# DDR3.net
KiCad netlist of a schematic drawn in Altium Designer
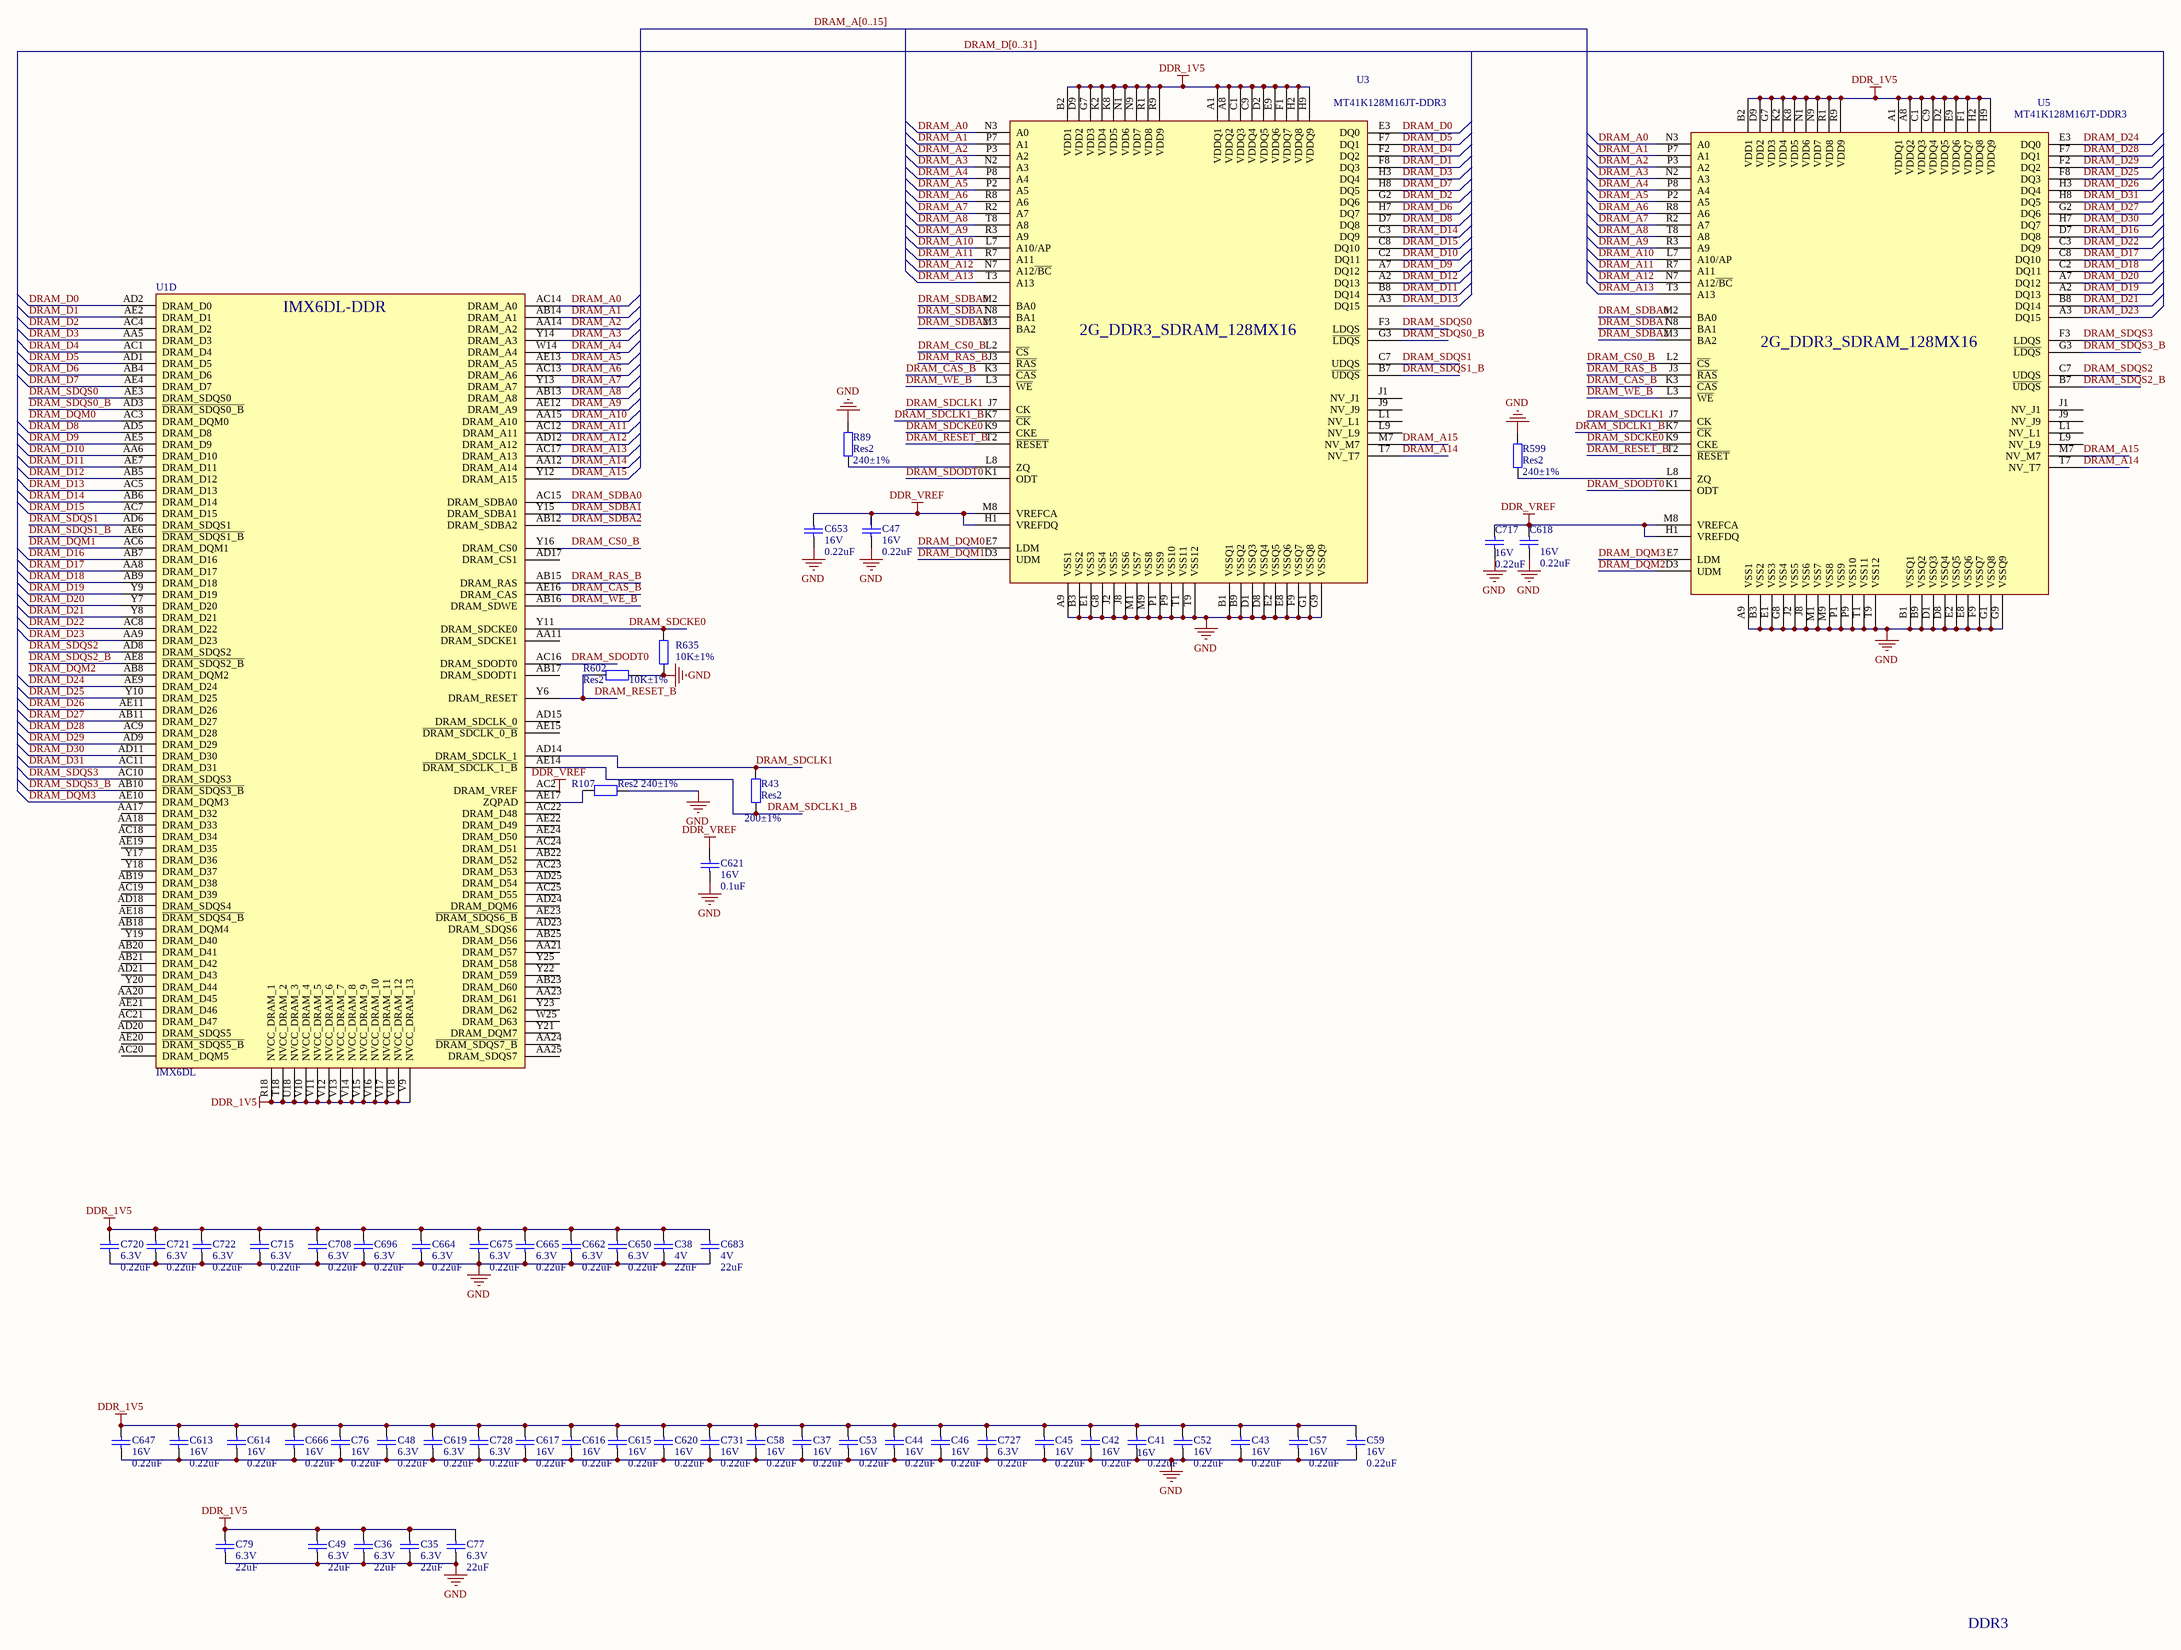
[diagram p0: DDR3.SchDoc]

(export (version "E")
  (design (tool "Eeschema 10.0.6"))
  (components
    (comp (ref "C35")
      (value "6.3V")
      (footprint "0805")
      (description "Capacitor")
      (fields (field (name "ALTIUM_VALUE") "22uF") (field (name "PUBLISHER") "Altium Limited"))
      (libsource (lib "Miscellaneous Devices") (part "Cap"))
    )
    (comp (ref "C36")
      (value "6.3V")
      (footprint "0805")
      (description "Capacitor")
      (fields (field (name "ALTIUM_VALUE") "22uF") (field (name "PUBLISHER") "Altium Limited"))
      (libsource (lib "Miscellaneous Devices") (part "Cap"))
    )
    (comp (ref "C37")
      (value "16V")
      (footprint "0402")
      (description "Capacitor")
      (fields (field (name "ALTIUM_VALUE") "0.22uF") (field (name "PUBLISHER") "Altium Limited"))
      (libsource (lib "Miscellaneous Devices") (part "Cap"))
    )
    (comp (ref "C38")
      (value "4V")
      (footprint "0603")
      (description "Capacitor")
      (fields (field (name "ALTIUM_VALUE") "22uF") (field (name "PUBLISHER") "Altium Limited"))
      (libsource (lib "Miscellaneous Devices") (part "Cap"))
    )
    (comp (ref "C41")
      (value "16V")
      (footprint "0402")
      (description "Capacitor")
      (fields (field (name "ALTIUM_VALUE") "0.22uF") (field (name "PUBLISHER") "Altium Limited"))
      (libsource (lib "Miscellaneous Devices") (part "Cap"))
    )
    (comp (ref "C42")
      (value "16V")
      (footprint "0402")
      (description "Capacitor")
      (fields (field (name "ALTIUM_VALUE") "0.22uF") (field (name "PUBLISHER") "Altium Limited"))
      (libsource (lib "Miscellaneous Devices") (part "Cap"))
    )
    (comp (ref "C43")
      (value "16V")
      (footprint "0402")
      (description "Capacitor")
      (fields (field (name "ALTIUM_VALUE") "0.22uF") (field (name "PUBLISHER") "Altium Limited"))
      (libsource (lib "Miscellaneous Devices") (part "Cap"))
    )
    (comp (ref "C44")
      (value "16V")
      (footprint "0402")
      (description "Capacitor")
      (fields (field (name "ALTIUM_VALUE") "0.22uF") (field (name "PUBLISHER") "Altium Limited"))
      (libsource (lib "Miscellaneous Devices") (part "Cap"))
    )
    (comp (ref "C45")
      (value "16V")
      (footprint "0402")
      (description "Capacitor")
      (fields (field (name "ALTIUM_VALUE") "0.22uF") (field (name "PUBLISHER") "Altium Limited"))
      (libsource (lib "Miscellaneous Devices") (part "Cap"))
    )
    (comp (ref "C46")
      (value "16V")
      (footprint "0402")
      (description "Capacitor")
      (fields (field (name "ALTIUM_VALUE") "0.22uF") (field (name "PUBLISHER") "Altium Limited"))
      (libsource (lib "Miscellaneous Devices") (part "Cap"))
    )
    (comp (ref "C47")
      (value "16V")
      (footprint "0402")
      (description "Capacitor")
      (fields (field (name "ALTIUM_VALUE") "0.22uF") (field (name "PUBLISHER") "Altium Limited"))
      (libsource (lib "Miscellaneous Devices") (part "Cap"))
    )
    (comp (ref "C48")
      (value "6.3V")
      (footprint "0201")
      (description "Capacitor")
      (fields (field (name "ALTIUM_VALUE") "0.22uF") (field (name "PUBLISHER") "Altium Limited"))
      (libsource (lib "Miscellaneous Devices") (part "Cap"))
    )
    (comp (ref "C49")
      (value "6.3V")
      (footprint "0805")
      (description "Capacitor")
      (fields (field (name "ALTIUM_VALUE") "22uF") (field (name "PUBLISHER") "Altium Limited"))
      (libsource (lib "Miscellaneous Devices") (part "Cap"))
    )
    (comp (ref "C52")
      (value "16V")
      (footprint "0402")
      (description "Capacitor")
      (fields (field (name "ALTIUM_VALUE") "0.22uF") (field (name "PUBLISHER") "Altium Limited"))
      (libsource (lib "Miscellaneous Devices") (part "Cap"))
    )
    (comp (ref "C53")
      (value "16V")
      (footprint "0402")
      (description "Capacitor")
      (fields (field (name "ALTIUM_VALUE") "0.22uF") (field (name "PUBLISHER") "Altium Limited"))
      (libsource (lib "Miscellaneous Devices") (part "Cap"))
    )
    (comp (ref "C57")
      (value "16V")
      (footprint "0402")
      (description "Capacitor")
      (fields (field (name "ALTIUM_VALUE") "0.22uF") (field (name "PUBLISHER") "Altium Limited"))
      (libsource (lib "Miscellaneous Devices") (part "Cap"))
    )
    (comp (ref "C58")
      (value "16V")
      (footprint "0402")
      (description "Capacitor")
      (fields (field (name "ALTIUM_VALUE") "0.22uF") (field (name "PUBLISHER") "Altium Limited"))
      (libsource (lib "Miscellaneous Devices") (part "Cap"))
    )
    (comp (ref "C59")
      (value "16V")
      (footprint "0402")
      (description "Capacitor")
      (fields (field (name "ALTIUM_VALUE") "0.22uF") (field (name "PUBLISHER") "Altium Limited"))
      (libsource (lib "Miscellaneous Devices") (part "Cap"))
    )
    (comp (ref "C76")
      (value "16V")
      (footprint "0402")
      (description "Capacitor")
      (fields (field (name "ALTIUM_VALUE") "0.22uF") (field (name "PUBLISHER") "Altium Limited"))
      (libsource (lib "Miscellaneous Devices") (part "Cap"))
    )
    (comp (ref "C77")
      (value "6.3V")
      (footprint "0805")
      (description "Capacitor")
      (fields (field (name "ALTIUM_VALUE") "22uF") (field (name "PUBLISHER") "Altium Limited"))
      (libsource (lib "Miscellaneous Devices") (part "Cap"))
    )
    (comp (ref "C79")
      (value "6.3V")
      (footprint "0805")
      (description "Capacitor")
      (fields (field (name "ALTIUM_VALUE") "22uF") (field (name "PUBLISHER") "Altium Limited"))
      (libsource (lib "Miscellaneous Devices") (part "Cap"))
    )
    (comp (ref "C613")
      (value "16V")
      (footprint "0402")
      (description "Capacitor")
      (fields (field (name "ALTIUM_VALUE") "0.22uF") (field (name "PUBLISHER") "Altium Limited"))
      (libsource (lib "Miscellaneous Devices") (part "Cap"))
    )
    (comp (ref "C614")
      (value "16V")
      (footprint "0402")
      (description "Capacitor")
      (fields (field (name "ALTIUM_VALUE") "0.22uF") (field (name "PUBLISHER") "Altium Limited"))
      (libsource (lib "Miscellaneous Devices") (part "Cap"))
    )
    (comp (ref "C615")
      (value "16V")
      (footprint "0402")
      (description "Capacitor")
      (fields (field (name "ALTIUM_VALUE") "0.22uF") (field (name "PUBLISHER") "Altium Limited"))
      (libsource (lib "Miscellaneous Devices") (part "Cap"))
    )
    (comp (ref "C616")
      (value "16V")
      (footprint "0402")
      (description "Capacitor")
      (fields (field (name "ALTIUM_VALUE") "0.22uF") (field (name "PUBLISHER") "Altium Limited"))
      (libsource (lib "Miscellaneous Devices") (part "Cap"))
    )
    (comp (ref "C617")
      (value "16V")
      (footprint "0402")
      (description "Capacitor")
      (fields (field (name "ALTIUM_VALUE") "0.22uF") (field (name "PUBLISHER") "Altium Limited"))
      (libsource (lib "Miscellaneous Devices") (part "Cap"))
    )
    (comp (ref "C618")
      (value "16V")
      (footprint "0402")
      (description "Capacitor")
      (fields (field (name "ALTIUM_VALUE") "0.22uF") (field (name "PUBLISHER") "Altium Limited"))
      (libsource (lib "Miscellaneous Devices") (part "Cap"))
    )
    (comp (ref "C619")
      (value "6.3V")
      (footprint "0201")
      (description "Capacitor")
      (fields (field (name "ALTIUM_VALUE") "0.22uF") (field (name "PUBLISHER") "Altium Limited"))
      (libsource (lib "Miscellaneous Devices") (part "Cap"))
    )
    (comp (ref "C620")
      (value "16V")
      (footprint "0402")
      (description "Capacitor")
      (fields (field (name "ALTIUM_VALUE") "0.22uF") (field (name "PUBLISHER") "Altium Limited"))
      (libsource (lib "Miscellaneous Devices") (part "Cap"))
    )
    (comp (ref "C621")
      (value "16V")
      (footprint "0402")
      (description "Capacitor")
      (fields (field (name "ALTIUM_VALUE") "0.1uF") (field (name "PUBLISHER") "Altium Limited"))
      (libsource (lib "Miscellaneous Devices") (part "Cap"))
    )
    (comp (ref "C647")
      (value "16V")
      (footprint "0402")
      (description "Capacitor")
      (fields (field (name "ALTIUM_VALUE") "0.22uF") (field (name "PUBLISHER") "Altium Limited"))
      (libsource (lib "Miscellaneous Devices") (part "Cap"))
    )
    (comp (ref "C650")
      (value "6.3V")
      (footprint "0201")
      (description "Capacitor")
      (fields (field (name "ALTIUM_VALUE") "0.22uF") (field (name "PUBLISHER") "Altium Limited"))
      (libsource (lib "Miscellaneous Devices") (part "Cap"))
    )
    (comp (ref "C653")
      (value "16V")
      (footprint "0402")
      (description "Capacitor")
      (fields (field (name "ALTIUM_VALUE") "0.22uF") (field (name "PUBLISHER") "Altium Limited"))
      (libsource (lib "Miscellaneous Devices") (part "Cap"))
    )
    (comp (ref "C662")
      (value "6.3V")
      (footprint "0201")
      (description "Capacitor")
      (fields (field (name "ALTIUM_VALUE") "0.22uF") (field (name "PUBLISHER") "Altium Limited"))
      (libsource (lib "Miscellaneous Devices") (part "Cap"))
    )
    (comp (ref "C664")
      (value "6.3V")
      (footprint "0201")
      (description "Capacitor")
      (fields (field (name "ALTIUM_VALUE") "0.22uF") (field (name "PUBLISHER") "Altium Limited"))
      (libsource (lib "Miscellaneous Devices") (part "Cap"))
    )
    (comp (ref "C665")
      (value "6.3V")
      (footprint "0201")
      (description "Capacitor")
      (fields (field (name "ALTIUM_VALUE") "0.22uF") (field (name "PUBLISHER") "Altium Limited"))
      (libsource (lib "Miscellaneous Devices") (part "Cap"))
    )
    (comp (ref "C666")
      (value "16V")
      (footprint "0402")
      (description "Capacitor")
      (fields (field (name "ALTIUM_VALUE") "0.22uF") (field (name "PUBLISHER") "Altium Limited"))
      (libsource (lib "Miscellaneous Devices") (part "Cap"))
    )
    (comp (ref "C675")
      (value "6.3V")
      (footprint "0201")
      (description "Capacitor")
      (fields (field (name "ALTIUM_VALUE") "0.22uF") (field (name "PUBLISHER") "Altium Limited"))
      (libsource (lib "Miscellaneous Devices") (part "Cap"))
    )
    (comp (ref "C683")
      (value "4V")
      (footprint "0603")
      (description "Capacitor")
      (fields (field (name "ALTIUM_VALUE") "22uF") (field (name "PUBLISHER") "Altium Limited"))
      (libsource (lib "Miscellaneous Devices") (part "Cap"))
    )
    (comp (ref "C696")
      (value "6.3V")
      (footprint "0201")
      (description "Capacitor")
      (fields (field (name "ALTIUM_VALUE") "0.22uF") (field (name "PUBLISHER") "Altium Limited"))
      (libsource (lib "Miscellaneous Devices") (part "Cap"))
    )
    (comp (ref "C708")
      (value "6.3V")
      (footprint "0201")
      (description "Capacitor")
      (fields (field (name "ALTIUM_VALUE") "0.22uF") (field (name "PUBLISHER") "Altium Limited"))
      (libsource (lib "Miscellaneous Devices") (part "Cap"))
    )
    (comp (ref "C715")
      (value "6.3V")
      (footprint "0201")
      (description "Capacitor")
      (fields (field (name "ALTIUM_VALUE") "0.22uF") (field (name "PUBLISHER") "Altium Limited"))
      (libsource (lib "Miscellaneous Devices") (part "Cap"))
    )
    (comp (ref "C717")
      (value "16V")
      (footprint "0402")
      (description "Capacitor")
      (fields (field (name "ALTIUM_VALUE") "0.22uF") (field (name "PUBLISHER") "Altium Limited"))
      (libsource (lib "Miscellaneous Devices") (part "Cap"))
    )
    (comp (ref "C720")
      (value "6.3V")
      (footprint "0201")
      (description "Capacitor")
      (fields (field (name "ALTIUM_VALUE") "0.22uF") (field (name "PUBLISHER") "Altium Limited"))
      (libsource (lib "Miscellaneous Devices") (part "Cap"))
    )
    (comp (ref "C721")
      (value "6.3V")
      (footprint "0201")
      (description "Capacitor")
      (fields (field (name "ALTIUM_VALUE") "0.22uF") (field (name "PUBLISHER") "Altium Limited"))
      (libsource (lib "Miscellaneous Devices") (part "Cap"))
    )
    (comp (ref "C722")
      (value "6.3V")
      (footprint "0201")
      (description "Capacitor")
      (fields (field (name "ALTIUM_VALUE") "0.22uF") (field (name "PUBLISHER") "Altium Limited"))
      (libsource (lib "Miscellaneous Devices") (part "Cap"))
    )
    (comp (ref "C727")
      (value "6.3V")
      (footprint "0201")
      (description "Capacitor")
      (fields (field (name "ALTIUM_VALUE") "0.22uF") (field (name "PUBLISHER") "Altium Limited"))
      (libsource (lib "Miscellaneous Devices") (part "Cap"))
    )
    (comp (ref "C728")
      (value "6.3V")
      (footprint "0201")
      (description "Capacitor")
      (fields (field (name "ALTIUM_VALUE") "0.22uF") (field (name "PUBLISHER") "Altium Limited"))
      (libsource (lib "Miscellaneous Devices") (part "Cap"))
    )
    (comp (ref "C731")
      (value "16V")
      (footprint "0402")
      (description "Capacitor")
      (fields (field (name "ALTIUM_VALUE") "0.22uF") (field (name "PUBLISHER") "Altium Limited"))
      (libsource (lib "Miscellaneous Devices") (part "Cap"))
    )
    (comp (ref "R43")
      (value "Res2")
      (footprint "0402")
      (description "Resistor")
      (fields (field (name "ALTIUM_VALUE") "200±1%") (field (name "PUBLISHER") "Altium Limited"))
      (libsource (lib "") (part "Res2_1"))
    )
    (comp (ref "R89")
      (value "Res2")
      (footprint "0402")
      (description "Resistor")
      (fields (field (name "ALTIUM_VALUE") "240±1%") (field (name "PUBLISHER") "Altium Limited"))
      (libsource (lib "Miscellaneous Devices") (part "Res2"))
    )
    (comp (ref "R107")
      (value "Res2")
      (footprint "0402")
      (description "Resistor")
      (fields (field (name "ALTIUM_VALUE") "240±1%") (field (name "PUBLISHER") "Altium Limited"))
      (libsource (lib "") (part "Res2_2"))
    )
    (comp (ref "R599")
      (value "Res2")
      (footprint "0402")
      (description "Resistor")
      (fields (field (name "ALTIUM_VALUE") "240±1%") (field (name "PUBLISHER") "Altium Limited"))
      (libsource (lib "Miscellaneous Devices") (part "Res2"))
    )
    (comp (ref "R602")
      (value "Res2")
      (footprint "0402")
      (description "Resistor")
      (fields (field (name "ALTIUM_VALUE") "10K±1%") (field (name "PUBLISHER") "Altium Limited"))
      (libsource (lib "") (part "Res2_2"))
    )
    (comp (ref "R635")
      (value "10K±1%")
      (footprint "0402")
      (description "Resistor")
      (fields (field (name "Comment") "Res2") (field (name "PUBLISHER") "Altium Limited"))
      (libsource (lib "") (part "Res2_1"))
    )
    (comp (ref "U1")
      (value "IMX6DL")
      (footprint "IMX6DL-BGA624x25")
      (libsource (lib "IMX6DL") (part "IMX6DL"))
    )
    (comp (ref "U3")
      (value "MT41K128M16JT-DDR3")
      (footprint "MT41K128M16JT-BGA96")
      (libsource (lib "IMX6DL") (part "MT41K128M16JT-DDR3"))
    )
    (comp (ref "U5")
      (value "MT41K128M16JT-DDR3")
      (footprint "MT41K128M16JT-BGA96")
      (libsource (lib "IMX6DL") (part "MT41K128M16JT-DDR3"))
    )
  )
  (nets
    (net (code "1") (name "/DRAM_A0") (class "Default")
      (node (ref "U1") (pin "AC14") (pinfunction "DRAM_A0_AC14") (pintype "passive"))
      (node (ref "U3") (pin "N3") (pinfunction "A0_N3") (pintype "passive"))
      (node (ref "U5") (pin "N3") (pinfunction "A0_N3") (pintype "passive"))
    )
    (net (code "2") (name "/DRAM_A1") (class "Default")
      (node (ref "U1") (pin "AB14") (pinfunction "DRAM_A1_AB14") (pintype "passive"))
      (node (ref "U3") (pin "P7") (pinfunction "A1_P7") (pintype "passive"))
      (node (ref "U5") (pin "P7") (pinfunction "A1_P7") (pintype "passive"))
    )
    (net (code "3") (name "/DRAM_A2") (class "Default")
      (node (ref "U1") (pin "AA14") (pinfunction "DRAM_A2_AA14") (pintype "passive"))
      (node (ref "U3") (pin "P3") (pinfunction "A2_P3") (pintype "passive"))
      (node (ref "U5") (pin "P3") (pinfunction "A2_P3") (pintype "passive"))
    )
    (net (code "4") (name "/DRAM_A3") (class "Default")
      (node (ref "U1") (pin "Y14") (pinfunction "DRAM_A3_Y14") (pintype "passive"))
      (node (ref "U3") (pin "N2") (pinfunction "A3_N2") (pintype "passive"))
      (node (ref "U5") (pin "N2") (pinfunction "A3_N2") (pintype "passive"))
    )
    (net (code "5") (name "/DRAM_A4") (class "Default")
      (node (ref "U1") (pin "W14") (pinfunction "DRAM_A4_W14") (pintype "passive"))
      (node (ref "U3") (pin "P8") (pinfunction "A4_P8") (pintype "passive"))
      (node (ref "U5") (pin "P8") (pinfunction "A4_P8") (pintype "passive"))
    )
    (net (code "6") (name "/DRAM_A5") (class "Default")
      (node (ref "U1") (pin "AE13") (pinfunction "DRAM_A5_AE13") (pintype "passive"))
      (node (ref "U3") (pin "P2") (pinfunction "A5_P2") (pintype "passive"))
      (node (ref "U5") (pin "P2") (pinfunction "A5_P2") (pintype "passive"))
    )
    (net (code "7") (name "/DRAM_A6") (class "Default")
      (node (ref "U1") (pin "AC13") (pinfunction "DRAM_A6_AC13") (pintype "passive"))
      (node (ref "U3") (pin "R8") (pinfunction "A6_R8") (pintype "passive"))
      (node (ref "U5") (pin "R8") (pinfunction "A6_R8") (pintype "passive"))
    )
    (net (code "8") (name "/DRAM_A7") (class "Default")
      (node (ref "U1") (pin "Y13") (pinfunction "DRAM_A7_Y13") (pintype "passive"))
      (node (ref "U3") (pin "R2") (pinfunction "A7_R2") (pintype "passive"))
      (node (ref "U5") (pin "R2") (pinfunction "A7_R2") (pintype "passive"))
    )
    (net (code "9") (name "/DRAM_A8") (class "Default")
      (node (ref "U1") (pin "AB13") (pinfunction "DRAM_A8_AB13") (pintype "passive"))
      (node (ref "U3") (pin "T8") (pinfunction "A8_T8") (pintype "passive"))
      (node (ref "U5") (pin "T8") (pinfunction "A8_T8") (pintype "passive"))
    )
    (net (code "10") (name "/DRAM_A9") (class "Default")
      (node (ref "U1") (pin "AE12") (pinfunction "DRAM_A9_AE12") (pintype "passive"))
      (node (ref "U3") (pin "R3") (pinfunction "A9_R3") (pintype "passive"))
      (node (ref "U5") (pin "R3") (pinfunction "A9_R3") (pintype "passive"))
    )
    (net (code "11") (name "/DRAM_A10") (class "Default")
      (node (ref "U1") (pin "AA15") (pinfunction "DRAM_A10_AA15") (pintype "passive"))
      (node (ref "U3") (pin "L7") (pinfunction "A10/AP_L7") (pintype "passive"))
      (node (ref "U5") (pin "L7") (pinfunction "A10/AP_L7") (pintype "passive"))
    )
    (net (code "12") (name "/DRAM_A11") (class "Default")
      (node (ref "U1") (pin "AC12") (pinfunction "DRAM_A11_AC12") (pintype "passive"))
      (node (ref "U3") (pin "R7") (pinfunction "A11_R7") (pintype "passive"))
      (node (ref "U5") (pin "R7") (pinfunction "A11_R7") (pintype "passive"))
    )
    (net (code "13") (name "/DRAM_A12") (class "Default")
      (node (ref "U1") (pin "AD12") (pinfunction "DRAM_A12_AD12") (pintype "passive"))
      (node (ref "U3") (pin "N7") (pinfunction "A12~{/BC}_N7") (pintype "passive"))
      (node (ref "U5") (pin "N7") (pinfunction "A12~{/BC}_N7") (pintype "passive"))
    )
    (net (code "14") (name "/DRAM_A13") (class "Default")
      (node (ref "U1") (pin "AC17") (pinfunction "DRAM_A13_AC17") (pintype "passive"))
      (node (ref "U3") (pin "T3") (pinfunction "A13_T3") (pintype "passive"))
      (node (ref "U5") (pin "T3") (pinfunction "A13_T3") (pintype "passive"))
    )
    (net (code "15") (name "/DRAM_A14") (class "Default")
      (node (ref "U1") (pin "AA12") (pinfunction "DRAM_A14_AA12") (pintype "passive"))
      (node (ref "U3") (pin "T7") (pinfunction "NV_T7_T7") (pintype "passive"))
      (node (ref "U5") (pin "T7") (pinfunction "NV_T7_T7") (pintype "passive"))
    )
    (net (code "16") (name "/DRAM_A15") (class "Default")
      (node (ref "U1") (pin "Y12") (pinfunction "DRAM_A15_Y12") (pintype "passive"))
      (node (ref "U3") (pin "M7") (pinfunction "NV_M7_M7") (pintype "passive"))
      (node (ref "U5") (pin "M7") (pinfunction "NV_M7_M7") (pintype "passive"))
    )
    (net (code "18") (name "/DRAM_CAS_B") (class "Default")
      (node (ref "U1") (pin "AE16") (pinfunction "DRAM_CAS_AE16") (pintype "passive"))
      (node (ref "U3") (pin "K3") (pinfunction "~{CAS}_K3") (pintype "passive"))
      (node (ref "U5") (pin "K3") (pinfunction "~{CAS}_K3") (pintype "passive"))
    )
    (net (code "19") (name "/DRAM_CS0_B") (class "Default")
      (node (ref "U1") (pin "Y16") (pinfunction "DRAM_CS0_Y16") (pintype "passive"))
      (node (ref "U3") (pin "L2") (pinfunction "~{CS}_L2") (pintype "passive"))
      (node (ref "U5") (pin "L2") (pinfunction "~{CS}_L2") (pintype "passive"))
    )
    (net (code "20") (name "/DRAM_D0") (class "Default")
      (node (ref "U1") (pin "AD2") (pinfunction "DRAM_D0_AD2") (pintype "passive"))
      (node (ref "U3") (pin "E3") (pinfunction "DQ0_E3") (pintype "passive"))
    )
    (net (code "21") (name "/DRAM_D1") (class "Default")
      (node (ref "U1") (pin "AE2") (pinfunction "DRAM_D1_AE2") (pintype "passive"))
      (node (ref "U3") (pin "F8") (pinfunction "DQ3_F8") (pintype "passive"))
    )
    (net (code "22") (name "/DRAM_D2") (class "Default")
      (node (ref "U1") (pin "AC4") (pinfunction "DRAM_D2_AC4") (pintype "passive"))
      (node (ref "U3") (pin "G2") (pinfunction "DQ6_G2") (pintype "passive"))
    )
    (net (code "23") (name "/DRAM_D3") (class "Default")
      (node (ref "U1") (pin "AA5") (pinfunction "DRAM_D3_AA5") (pintype "passive"))
      (node (ref "U3") (pin "H3") (pinfunction "DQ4_H3") (pintype "passive"))
    )
    (net (code "24") (name "/DRAM_D4") (class "Default")
      (node (ref "U1") (pin "AC1") (pinfunction "DRAM_D4_AC1") (pintype "passive"))
      (node (ref "U3") (pin "F2") (pinfunction "DQ2_F2") (pintype "passive"))
    )
    (net (code "25") (name "/DRAM_D5") (class "Default")
      (node (ref "U1") (pin "AD1") (pinfunction "DRAM_D5_AD1") (pintype "passive"))
      (node (ref "U3") (pin "F7") (pinfunction "DQ1_F7") (pintype "passive"))
    )
    (net (code "26") (name "/DRAM_D6") (class "Default")
      (node (ref "U1") (pin "AB4") (pinfunction "DRAM_D6_AB4") (pintype "passive"))
      (node (ref "U3") (pin "H7") (pinfunction "DQ7_H7") (pintype "passive"))
    )
    (net (code "27") (name "/DRAM_D7") (class "Default")
      (node (ref "U1") (pin "AE4") (pinfunction "DRAM_D7_AE4") (pintype "passive"))
      (node (ref "U3") (pin "H8") (pinfunction "DQ5_H8") (pintype "passive"))
    )
    (net (code "28") (name "/DRAM_D8") (class "Default")
      (node (ref "U1") (pin "AD5") (pinfunction "DRAM_D8_AD5") (pintype "passive"))
      (node (ref "U3") (pin "D7") (pinfunction "DQ8_D7") (pintype "passive"))
    )
    (net (code "29") (name "/DRAM_D9") (class "Default")
      (node (ref "U1") (pin "AE5") (pinfunction "DRAM_D9_AE5") (pintype "passive"))
      (node (ref "U3") (pin "A7") (pinfunction "DQ12_A7") (pintype "passive"))
    )
    (net (code "30") (name "/DRAM_D10") (class "Default")
      (node (ref "U1") (pin "AA6") (pinfunction "DRAM_D10_AA6") (pintype "passive"))
      (node (ref "U3") (pin "C2") (pinfunction "DQ11_C2") (pintype "passive"))
    )
    (net (code "31") (name "/DRAM_D11") (class "Default")
      (node (ref "U1") (pin "AE7") (pinfunction "DRAM_D11_AE7") (pintype "passive"))
      (node (ref "U3") (pin "B8") (pinfunction "DQ14_B8") (pintype "passive"))
    )
    (net (code "32") (name "/DRAM_D12") (class "Default")
      (node (ref "U1") (pin "AB5") (pinfunction "DRAM_D12_AB5") (pintype "passive"))
      (node (ref "U3") (pin "A2") (pinfunction "DQ13_A2") (pintype "passive"))
    )
    (net (code "33") (name "/DRAM_D13") (class "Default")
      (node (ref "U1") (pin "AC5") (pinfunction "DRAM_D13_AC5") (pintype "passive"))
      (node (ref "U3") (pin "A3") (pinfunction "DQ15_A3") (pintype "passive"))
    )
    (net (code "34") (name "/DRAM_D14") (class "Default")
      (node (ref "U1") (pin "AB6") (pinfunction "DRAM_D14_AB6") (pintype "passive"))
      (node (ref "U3") (pin "C3") (pinfunction "DQ9_C3") (pintype "passive"))
    )
    (net (code "35") (name "/DRAM_D15") (class "Default")
      (node (ref "U1") (pin "AC7") (pinfunction "DRAM_D15_AC7") (pintype "passive"))
      (node (ref "U3") (pin "C8") (pinfunction "DQ10_C8") (pintype "passive"))
    )
    (net (code "36") (name "/DRAM_D16") (class "Default")
      (node (ref "U1") (pin "AB7") (pinfunction "DRAM_D16_AB7") (pintype "passive"))
      (node (ref "U5") (pin "D7") (pinfunction "DQ8_D7") (pintype "passive"))
    )
    (net (code "37") (name "/DRAM_D17") (class "Default")
      (node (ref "U1") (pin "AA8") (pinfunction "DRAM_D17_AA8") (pintype "passive"))
      (node (ref "U5") (pin "C8") (pinfunction "DQ10_C8") (pintype "passive"))
    )
    (net (code "38") (name "/DRAM_D18") (class "Default")
      (node (ref "U1") (pin "AB9") (pinfunction "DRAM_D18_AB9") (pintype "passive"))
      (node (ref "U5") (pin "C2") (pinfunction "DQ11_C2") (pintype "passive"))
    )
    (net (code "39") (name "/DRAM_D19") (class "Default")
      (node (ref "U1") (pin "Y9") (pinfunction "DRAM_D19_Y9") (pintype "passive"))
      (node (ref "U5") (pin "A2") (pinfunction "DQ13_A2") (pintype "passive"))
    )
    (net (code "40") (name "/DRAM_D20") (class "Default")
      (node (ref "U1") (pin "Y7") (pinfunction "DRAM_D20_Y7") (pintype "passive"))
      (node (ref "U5") (pin "A7") (pinfunction "DQ12_A7") (pintype "passive"))
    )
    (net (code "41") (name "/DRAM_D21") (class "Default")
      (node (ref "U1") (pin "Y8") (pinfunction "DRAM_D21_Y8") (pintype "passive"))
      (node (ref "U5") (pin "B8") (pinfunction "DQ14_B8") (pintype "passive"))
    )
    (net (code "42") (name "/DRAM_D22") (class "Default")
      (node (ref "U1") (pin "AC8") (pinfunction "DRAM_D22_AC8") (pintype "passive"))
      (node (ref "U5") (pin "C3") (pinfunction "DQ9_C3") (pintype "passive"))
    )
    (net (code "43") (name "/DRAM_D23") (class "Default")
      (node (ref "U1") (pin "AA9") (pinfunction "DRAM_D23_AA9") (pintype "passive"))
      (node (ref "U5") (pin "A3") (pinfunction "DQ15_A3") (pintype "passive"))
    )
    (net (code "44") (name "/DRAM_D24") (class "Default")
      (node (ref "U1") (pin "AE9") (pinfunction "DRAM_D24_AE9") (pintype "passive"))
      (node (ref "U5") (pin "E3") (pinfunction "DQ0_E3") (pintype "passive"))
    )
    (net (code "45") (name "/DRAM_D25") (class "Default")
      (node (ref "U1") (pin "Y10") (pinfunction "DRAM_D25_Y10") (pintype "passive"))
      (node (ref "U5") (pin "F8") (pinfunction "DQ3_F8") (pintype "passive"))
    )
    (net (code "46") (name "/DRAM_D26") (class "Default")
      (node (ref "U1") (pin "AE11") (pinfunction "DRAM_D26_AE11") (pintype "passive"))
      (node (ref "U5") (pin "H3") (pinfunction "DQ4_H3") (pintype "passive"))
    )
    (net (code "47") (name "/DRAM_D27") (class "Default")
      (node (ref "U1") (pin "AB11") (pinfunction "DRAM_D27_AB11") (pintype "passive"))
      (node (ref "U5") (pin "G2") (pinfunction "DQ6_G2") (pintype "passive"))
    )
    (net (code "48") (name "/DRAM_D28") (class "Default")
      (node (ref "U1") (pin "AC9") (pinfunction "DRAM_D28_AC9") (pintype "passive"))
      (node (ref "U5") (pin "F7") (pinfunction "DQ1_F7") (pintype "passive"))
    )
    (net (code "49") (name "/DRAM_D29") (class "Default")
      (node (ref "U1") (pin "AD9") (pinfunction "DRAM_D29_AD9") (pintype "passive"))
      (node (ref "U5") (pin "F2") (pinfunction "DQ2_F2") (pintype "passive"))
    )
    (net (code "50") (name "/DRAM_D30") (class "Default")
      (node (ref "U1") (pin "AD11") (pinfunction "DRAM_D30_AD11") (pintype "passive"))
      (node (ref "U5") (pin "H7") (pinfunction "DQ7_H7") (pintype "passive"))
    )
    (net (code "51") (name "/DRAM_D31") (class "Default")
      (node (ref "U1") (pin "AC11") (pinfunction "DRAM_D31_AC11") (pintype "passive"))
      (node (ref "U5") (pin "H8") (pinfunction "DQ5_H8") (pintype "passive"))
    )
    (net (code "52") (name "/DRAM_DQM0") (class "Default")
      (node (ref "U1") (pin "AC3") (pinfunction "DRAM_DQM0_AC3") (pintype "passive"))
      (node (ref "U3") (pin "E7") (pinfunction "LDM_E7") (pintype "passive"))
    )
    (net (code "53") (name "/DRAM_DQM1") (class "Default")
      (node (ref "U1") (pin "AC6") (pinfunction "DRAM_DQM1_AC6") (pintype "passive"))
      (node (ref "U3") (pin "D3") (pinfunction "UDM_D3") (pintype "passive"))
    )
    (net (code "54") (name "/DRAM_DQM2") (class "Default")
      (node (ref "U1") (pin "AB8") (pinfunction "DRAM_DQM2_AB8") (pintype "passive"))
      (node (ref "U5") (pin "D3") (pinfunction "UDM_D3") (pintype "passive"))
    )
    (net (code "55") (name "/DRAM_DQM3") (class "Default")
      (node (ref "U1") (pin "AE10") (pinfunction "DRAM_DQM3_AE10") (pintype "passive"))
      (node (ref "U5") (pin "E7") (pinfunction "LDM_E7") (pintype "passive"))
    )
    (net (code "57") (name "/DRAM_RAS_B") (class "Default")
      (node (ref "U1") (pin "AB15") (pinfunction "DRAM_RAS_AB15") (pintype "passive"))
      (node (ref "U3") (pin "J3") (pinfunction "~{RAS}_J3") (pintype "passive"))
      (node (ref "U5") (pin "J3") (pinfunction "~{RAS}_J3") (pintype "passive"))
    )
    (net (code "58") (name "/DRAM_RESET_B") (class "Default")
      (node (ref "R602") (pin "2") (pinfunction "2_2") (pintype "passive"))
      (node (ref "U1") (pin "Y6") (pinfunction "DRAM_RESET_Y6") (pintype "passive"))
      (node (ref "U3") (pin "T2") (pinfunction "~{RESET}_T2") (pintype "passive"))
      (node (ref "U5") (pin "T2") (pinfunction "~{RESET}_T2") (pintype "passive"))
    )
    (net (code "59") (name "/DRAM_SDBA0") (class "Default")
      (node (ref "U1") (pin "AC15") (pinfunction "DRAM_SDBA0_AC15") (pintype "passive"))
      (node (ref "U3") (pin "M2") (pinfunction "BA0_M2") (pintype "passive"))
      (node (ref "U5") (pin "M2") (pinfunction "BA0_M2") (pintype "passive"))
    )
    (net (code "60") (name "/DRAM_SDBA1") (class "Default")
      (node (ref "U1") (pin "Y15") (pinfunction "DRAM_SDBA1_Y15") (pintype "passive"))
      (node (ref "U3") (pin "N8") (pinfunction "BA1_N8") (pintype "passive"))
      (node (ref "U5") (pin "N8") (pinfunction "BA1_N8") (pintype "passive"))
    )
    (net (code "61") (name "/DRAM_SDBA2") (class "Default")
      (node (ref "U1") (pin "AB12") (pinfunction "DRAM_SDBA2_AB12") (pintype "passive"))
      (node (ref "U3") (pin "M3") (pinfunction "BA2_M3") (pintype "passive"))
      (node (ref "U5") (pin "M3") (pinfunction "BA2_M3") (pintype "passive"))
    )
    (net (code "62") (name "/DRAM_SDCKE0") (class "Default")
      (node (ref "R635") (pin "2") (pinfunction "2_2") (pintype "passive"))
      (node (ref "U1") (pin "Y11") (pinfunction "DRAM_SDCKE0_Y11") (pintype "passive"))
      (node (ref "U3") (pin "K9") (pinfunction "CKE_K9") (pintype "passive"))
      (node (ref "U5") (pin "K9") (pinfunction "CKE_K9") (pintype "passive"))
    )
    (net (code "63") (name "/DRAM_SDCLK1") (class "Default")
      (node (ref "R43") (pin "2") (pinfunction "2_2") (pintype "passive"))
      (node (ref "U1") (pin "AD14") (pinfunction "DRAM_SDCLK_1_AD14") (pintype "passive"))
      (node (ref "U3") (pin "J7") (pinfunction "CK_J7") (pintype "passive"))
      (node (ref "U5") (pin "J7") (pinfunction "CK_J7") (pintype "passive"))
    )
    (net (code "64") (name "/DRAM_SDCLK1_B") (class "Default")
      (node (ref "R43") (pin "1") (pinfunction "1_1") (pintype "passive"))
      (node (ref "U1") (pin "AE14") (pinfunction "~{DRAM_SDCLK_1_B}_AE14") (pintype "passive"))
      (node (ref "U3") (pin "K7") (pinfunction "~{CK}_K7") (pintype "passive"))
      (node (ref "U5") (pin "K7") (pinfunction "~{CK}_K7") (pintype "passive"))
    )
    (net (code "65") (name "/DRAM_SDODT0") (class "Default")
      (node (ref "U1") (pin "AC16") (pinfunction "DRAM_SDODT0_AC16") (pintype "passive"))
      (node (ref "U3") (pin "K1") (pinfunction "ODT_K1") (pintype "passive"))
      (node (ref "U5") (pin "K1") (pinfunction "ODT_K1") (pintype "passive"))
    )
    (net (code "66") (name "/DRAM_SDQS0") (class "Default")
      (node (ref "U1") (pin "AE3") (pinfunction "DRAM_SDQS0_AE3") (pintype "passive"))
      (node (ref "U3") (pin "F3") (pinfunction "LDQS_F3") (pintype "passive"))
    )
    (net (code "67") (name "/DRAM_SDQS0_B") (class "Default")
      (node (ref "U1") (pin "AD3") (pinfunction "~{DRAM_SDQS0_B}_AD3") (pintype "passive"))
      (node (ref "U3") (pin "G3") (pinfunction "~{LDQS}_G3") (pintype "passive"))
    )
    (net (code "68") (name "/DRAM_SDQS1") (class "Default")
      (node (ref "U1") (pin "AD6") (pinfunction "DRAM_SDQS1_AD6") (pintype "passive"))
      (node (ref "U3") (pin "C7") (pinfunction "UDQS_C7") (pintype "passive"))
    )
    (net (code "69") (name "/DRAM_SDQS1_B") (class "Default")
      (node (ref "U1") (pin "AE6") (pinfunction "~{DRAM_SDQS1_B}_AE6") (pintype "passive"))
      (node (ref "U3") (pin "B7") (pinfunction "~{UDQS}_B7") (pintype "passive"))
    )
    (net (code "70") (name "/DRAM_SDQS2") (class "Default")
      (node (ref "U1") (pin "AD8") (pinfunction "DRAM_SDQS2_AD8") (pintype "passive"))
      (node (ref "U5") (pin "C7") (pinfunction "UDQS_C7") (pintype "passive"))
    )
    (net (code "71") (name "/DRAM_SDQS2_B") (class "Default")
      (node (ref "U1") (pin "AE8") (pinfunction "~{DRAM_SDQS2_B}_AE8") (pintype "passive"))
      (node (ref "U5") (pin "B7") (pinfunction "~{UDQS}_B7") (pintype "passive"))
    )
    (net (code "72") (name "/DRAM_SDQS3") (class "Default")
      (node (ref "U1") (pin "AC10") (pinfunction "DRAM_SDQS3_AC10") (pintype "passive"))
      (node (ref "U5") (pin "F3") (pinfunction "LDQS_F3") (pintype "passive"))
    )
    (net (code "73") (name "/DRAM_SDQS3_B") (class "Default")
      (node (ref "U1") (pin "AB10") (pinfunction "~{DRAM_SDQS3_B}_AB10") (pintype "passive"))
      (node (ref "U5") (pin "G3") (pinfunction "~{LDQS}_G3") (pintype "passive"))
    )
    (net (code "74") (name "/DRAM_WE_B") (class "Default")
      (node (ref "U1") (pin "AB16") (pinfunction "DRAM_SDWE_AB16") (pintype "passive"))
      (node (ref "U3") (pin "L3") (pinfunction "~{WE}_L3") (pintype "passive"))
      (node (ref "U5") (pin "L3") (pinfunction "~{WE}_L3") (pintype "passive"))
    )
    (net (code "75") (name "DDR_1V5") (class "Default")
      (node (ref "C35") (pin "2") (pinfunction "2_2") (pintype "passive"))
      (node (ref "C36") (pin "2") (pinfunction "2_2") (pintype "passive"))
      (node (ref "C37") (pin "2") (pinfunction "2_2") (pintype "passive"))
      (node (ref "C38") (pin "2") (pinfunction "2_2") (pintype "passive"))
      (node (ref "C41") (pin "2") (pinfunction "2_2") (pintype "passive"))
      (node (ref "C42") (pin "2") (pinfunction "2_2") (pintype "passive"))
      (node (ref "C43") (pin "2") (pinfunction "2_2") (pintype "passive"))
      (node (ref "C44") (pin "2") (pinfunction "2_2") (pintype "passive"))
      (node (ref "C45") (pin "2") (pinfunction "2_2") (pintype "passive"))
      (node (ref "C46") (pin "2") (pinfunction "2_2") (pintype "passive"))
      (node (ref "C48") (pin "2") (pinfunction "2_2") (pintype "passive"))
      (node (ref "C49") (pin "2") (pinfunction "2_2") (pintype "passive"))
      (node (ref "C52") (pin "2") (pinfunction "2_2") (pintype "passive"))
      (node (ref "C53") (pin "2") (pinfunction "2_2") (pintype "passive"))
      (node (ref "C57") (pin "2") (pinfunction "2_2") (pintype "passive"))
      (node (ref "C58") (pin "2") (pinfunction "2_2") (pintype "passive"))
      (node (ref "C59") (pin "2") (pinfunction "2_2") (pintype "passive"))
      (node (ref "C613") (pin "2") (pinfunction "2_2") (pintype "passive"))
      (node (ref "C614") (pin "2") (pinfunction "2_2") (pintype "passive"))
      (node (ref "C615") (pin "2") (pinfunction "2_2") (pintype "passive"))
      (node (ref "C616") (pin "2") (pinfunction "2_2") (pintype "passive"))
      (node (ref "C617") (pin "2") (pinfunction "2_2") (pintype "passive"))
      (node (ref "C619") (pin "2") (pinfunction "2_2") (pintype "passive"))
      (node (ref "C620") (pin "2") (pinfunction "2_2") (pintype "passive"))
      (node (ref "C647") (pin "2") (pinfunction "2_2") (pintype "passive"))
      (node (ref "C650") (pin "2") (pinfunction "2_2") (pintype "passive"))
      (node (ref "C662") (pin "2") (pinfunction "2_2") (pintype "passive"))
      (node (ref "C664") (pin "2") (pinfunction "2_2") (pintype "passive"))
      (node (ref "C665") (pin "2") (pinfunction "2_2") (pintype "passive"))
      (node (ref "C666") (pin "2") (pinfunction "2_2") (pintype "passive"))
      (node (ref "C675") (pin "2") (pinfunction "2_2") (pintype "passive"))
      (node (ref "C683") (pin "2") (pinfunction "2_2") (pintype "passive"))
      (node (ref "C696") (pin "2") (pinfunction "2_2") (pintype "passive"))
      (node (ref "C708") (pin "2") (pinfunction "2_2") (pintype "passive"))
      (node (ref "C715") (pin "2") (pinfunction "2_2") (pintype "passive"))
      (node (ref "C720") (pin "2") (pinfunction "2_2") (pintype "passive"))
      (node (ref "C721") (pin "2") (pinfunction "2_2") (pintype "passive"))
      (node (ref "C722") (pin "2") (pinfunction "2_2") (pintype "passive"))
      (node (ref "C727") (pin "2") (pinfunction "2_2") (pintype "passive"))
      (node (ref "C728") (pin "2") (pinfunction "2_2") (pintype "passive"))
      (node (ref "C731") (pin "2") (pinfunction "2_2") (pintype "passive"))
      (node (ref "C76") (pin "2") (pinfunction "2_2") (pintype "passive"))
      (node (ref "C77") (pin "2") (pinfunction "2_2") (pintype "passive"))
      (node (ref "C79") (pin "2") (pinfunction "2_2") (pintype "passive"))
      (node (ref "U1") (pin "R18") (pinfunction "NVCC_DRAM_1_R18") (pintype "passive"))
      (node (ref "U1") (pin "T18") (pinfunction "NVCC_DRAM_2_T18") (pintype "passive"))
      (node (ref "U1") (pin "U18") (pinfunction "NVCC_DRAM_3_U18") (pintype "passive"))
      (node (ref "U1") (pin "V10") (pinfunction "NVCC_DRAM_4_V10") (pintype "passive"))
      (node (ref "U1") (pin "V11") (pinfunction "NVCC_DRAM_5_V11") (pintype "passive"))
      (node (ref "U1") (pin "V12") (pinfunction "NVCC_DRAM_6_V12") (pintype "passive"))
      (node (ref "U1") (pin "V13") (pinfunction "NVCC_DRAM_7_V13") (pintype "passive"))
      (node (ref "U1") (pin "V14") (pinfunction "NVCC_DRAM_8_V14") (pintype "passive"))
      (node (ref "U1") (pin "V15") (pinfunction "NVCC_DRAM_9_V15") (pintype "passive"))
      (node (ref "U1") (pin "V16") (pinfunction "NVCC_DRAM_10_V16") (pintype "passive"))
      (node (ref "U1") (pin "V17") (pinfunction "NVCC_DRAM_11_V17") (pintype "passive"))
      (node (ref "U1") (pin "V18") (pinfunction "NVCC_DRAM_12_V18") (pintype "passive"))
      (node (ref "U1") (pin "V9") (pinfunction "NVCC_DRAM_13_V9") (pintype "passive"))
      (node (ref "U3") (pin "A1") (pinfunction "VDDQ1_A1") (pintype "passive"))
      (node (ref "U3") (pin "A8") (pinfunction "VDDQ2_A8") (pintype "passive"))
      (node (ref "U3") (pin "B2") (pinfunction "VDD1_B2") (pintype "passive"))
      (node (ref "U3") (pin "C1") (pinfunction "VDDQ3_C1") (pintype "passive"))
      (node (ref "U3") (pin "C9") (pinfunction "VDDQ4_C9") (pintype "passive"))
      (node (ref "U3") (pin "D2") (pinfunction "VDDQ5_D2") (pintype "passive"))
      (node (ref "U3") (pin "D9") (pinfunction "VDD2_D9") (pintype "passive"))
      (node (ref "U3") (pin "E9") (pinfunction "VDDQ6_E9") (pintype "passive"))
      (node (ref "U3") (pin "F1") (pinfunction "VDDQ7_F1") (pintype "passive"))
      (node (ref "U3") (pin "G7") (pinfunction "VDD3_G7") (pintype "passive"))
      (node (ref "U3") (pin "H2") (pinfunction "VDDQ8_H2") (pintype "passive"))
      (node (ref "U3") (pin "H9") (pinfunction "VDDQ9_H9") (pintype "passive"))
      (node (ref "U3") (pin "K2") (pinfunction "VDD4_K2") (pintype "passive"))
      (node (ref "U3") (pin "K8") (pinfunction "VDD5_K8") (pintype "passive"))
      (node (ref "U3") (pin "N1") (pinfunction "VDD6_N1") (pintype "passive"))
      (node (ref "U3") (pin "N9") (pinfunction "VDD7_N9") (pintype "passive"))
      (node (ref "U3") (pin "R1") (pinfunction "VDD8_R1") (pintype "passive"))
      (node (ref "U3") (pin "R9") (pinfunction "VDD9_R9") (pintype "passive"))
      (node (ref "U5") (pin "A1") (pinfunction "VDDQ1_A1") (pintype "passive"))
      (node (ref "U5") (pin "A8") (pinfunction "VDDQ2_A8") (pintype "passive"))
      (node (ref "U5") (pin "B2") (pinfunction "VDD1_B2") (pintype "passive"))
      (node (ref "U5") (pin "C1") (pinfunction "VDDQ3_C1") (pintype "passive"))
      (node (ref "U5") (pin "C9") (pinfunction "VDDQ4_C9") (pintype "passive"))
      (node (ref "U5") (pin "D2") (pinfunction "VDDQ5_D2") (pintype "passive"))
      (node (ref "U5") (pin "D9") (pinfunction "VDD2_D9") (pintype "passive"))
      (node (ref "U5") (pin "E9") (pinfunction "VDDQ6_E9") (pintype "passive"))
      (node (ref "U5") (pin "F1") (pinfunction "VDDQ7_F1") (pintype "passive"))
      (node (ref "U5") (pin "G7") (pinfunction "VDD3_G7") (pintype "passive"))
      (node (ref "U5") (pin "H2") (pinfunction "VDDQ8_H2") (pintype "passive"))
      (node (ref "U5") (pin "H9") (pinfunction "VDDQ9_H9") (pintype "passive"))
      (node (ref "U5") (pin "K2") (pinfunction "VDD4_K2") (pintype "passive"))
      (node (ref "U5") (pin "K8") (pinfunction "VDD5_K8") (pintype "passive"))
      (node (ref "U5") (pin "N1") (pinfunction "VDD6_N1") (pintype "passive"))
      (node (ref "U5") (pin "N9") (pinfunction "VDD7_N9") (pintype "passive"))
      (node (ref "U5") (pin "R1") (pinfunction "VDD8_R1") (pintype "passive"))
      (node (ref "U5") (pin "R9") (pinfunction "VDD9_R9") (pintype "passive"))
    )
    (net (code "76") (name "DDR_VREF") (class "Default")
      (node (ref "C47") (pin "2") (pinfunction "2_2") (pintype "passive"))
      (node (ref "C618") (pin "2") (pinfunction "2_2") (pintype "passive"))
      (node (ref "C621") (pin "2") (pinfunction "2_2") (pintype "passive"))
      (node (ref "C653") (pin "2") (pinfunction "2_2") (pintype "passive"))
      (node (ref "C717") (pin "2") (pinfunction "2_2") (pintype "passive"))
      (node (ref "U1") (pin "AC2") (pinfunction "DRAM_VREF_AC2") (pintype "passive"))
      (node (ref "U3") (pin "H1") (pinfunction "VREFDQ_H1") (pintype "passive"))
      (node (ref "U3") (pin "M8") (pinfunction "VREFCA_M8") (pintype "passive"))
      (node (ref "U5") (pin "H1") (pinfunction "VREFDQ_H1") (pintype "passive"))
      (node (ref "U5") (pin "M8") (pinfunction "VREFCA_M8") (pintype "passive"))
    )
    (net (code "77") (name "GND") (class "Default")
      (node (ref "C35") (pin "1") (pinfunction "1_1") (pintype "passive"))
      (node (ref "C36") (pin "1") (pinfunction "1_1") (pintype "passive"))
      (node (ref "C37") (pin "1") (pinfunction "1_1") (pintype "passive"))
      (node (ref "C38") (pin "1") (pinfunction "1_1") (pintype "passive"))
      (node (ref "C41") (pin "1") (pinfunction "1_1") (pintype "passive"))
      (node (ref "C42") (pin "1") (pinfunction "1_1") (pintype "passive"))
      (node (ref "C43") (pin "1") (pinfunction "1_1") (pintype "passive"))
      (node (ref "C44") (pin "1") (pinfunction "1_1") (pintype "passive"))
      (node (ref "C45") (pin "1") (pinfunction "1_1") (pintype "passive"))
      (node (ref "C46") (pin "1") (pinfunction "1_1") (pintype "passive"))
      (node (ref "C47") (pin "1") (pinfunction "1_1") (pintype "passive"))
      (node (ref "C48") (pin "1") (pinfunction "1_1") (pintype "passive"))
      (node (ref "C49") (pin "1") (pinfunction "1_1") (pintype "passive"))
      (node (ref "C52") (pin "1") (pinfunction "1_1") (pintype "passive"))
      (node (ref "C53") (pin "1") (pinfunction "1_1") (pintype "passive"))
      (node (ref "C57") (pin "1") (pinfunction "1_1") (pintype "passive"))
      (node (ref "C58") (pin "1") (pinfunction "1_1") (pintype "passive"))
      (node (ref "C59") (pin "1") (pinfunction "1_1") (pintype "passive"))
      (node (ref "C613") (pin "1") (pinfunction "1_1") (pintype "passive"))
      (node (ref "C614") (pin "1") (pinfunction "1_1") (pintype "passive"))
      (node (ref "C615") (pin "1") (pinfunction "1_1") (pintype "passive"))
      (node (ref "C616") (pin "1") (pinfunction "1_1") (pintype "passive"))
      (node (ref "C617") (pin "1") (pinfunction "1_1") (pintype "passive"))
      (node (ref "C618") (pin "1") (pinfunction "1_1") (pintype "passive"))
      (node (ref "C619") (pin "1") (pinfunction "1_1") (pintype "passive"))
      (node (ref "C620") (pin "1") (pinfunction "1_1") (pintype "passive"))
      (node (ref "C621") (pin "1") (pinfunction "1_1") (pintype "passive"))
      (node (ref "C647") (pin "1") (pinfunction "1_1") (pintype "passive"))
      (node (ref "C650") (pin "1") (pinfunction "1_1") (pintype "passive"))
      (node (ref "C653") (pin "1") (pinfunction "1_1") (pintype "passive"))
      (node (ref "C662") (pin "1") (pinfunction "1_1") (pintype "passive"))
      (node (ref "C664") (pin "1") (pinfunction "1_1") (pintype "passive"))
      (node (ref "C665") (pin "1") (pinfunction "1_1") (pintype "passive"))
      (node (ref "C666") (pin "1") (pinfunction "1_1") (pintype "passive"))
      (node (ref "C675") (pin "1") (pinfunction "1_1") (pintype "passive"))
      (node (ref "C683") (pin "1") (pinfunction "1_1") (pintype "passive"))
      (node (ref "C696") (pin "1") (pinfunction "1_1") (pintype "passive"))
      (node (ref "C708") (pin "1") (pinfunction "1_1") (pintype "passive"))
      (node (ref "C715") (pin "1") (pinfunction "1_1") (pintype "passive"))
      (node (ref "C717") (pin "1") (pinfunction "1_1") (pintype "passive"))
      (node (ref "C720") (pin "1") (pinfunction "1_1") (pintype "passive"))
      (node (ref "C721") (pin "1") (pinfunction "1_1") (pintype "passive"))
      (node (ref "C722") (pin "1") (pinfunction "1_1") (pintype "passive"))
      (node (ref "C727") (pin "1") (pinfunction "1_1") (pintype "passive"))
      (node (ref "C728") (pin "1") (pinfunction "1_1") (pintype "passive"))
      (node (ref "C731") (pin "1") (pinfunction "1_1") (pintype "passive"))
      (node (ref "C76") (pin "1") (pinfunction "1_1") (pintype "passive"))
      (node (ref "C77") (pin "1") (pinfunction "1_1") (pintype "passive"))
      (node (ref "C79") (pin "1") (pinfunction "1_1") (pintype "passive"))
      (node (ref "R107") (pin "1") (pinfunction "1_1") (pintype "passive"))
      (node (ref "R599") (pin "1") (pinfunction "1_1") (pintype "passive"))
      (node (ref "R602") (pin "1") (pinfunction "1_1") (pintype "passive"))
      (node (ref "R635") (pin "1") (pinfunction "1_1") (pintype "passive"))
      (node (ref "R89") (pin "1") (pinfunction "1_1") (pintype "passive"))
      (node (ref "U3") (pin "A9") (pinfunction "VSS1_A9") (pintype "passive"))
      (node (ref "U3") (pin "B1") (pinfunction "VSSQ1_B1") (pintype "passive"))
      (node (ref "U3") (pin "B3") (pinfunction "VSS2_B3") (pintype "passive"))
      (node (ref "U3") (pin "B9") (pinfunction "VSSQ2_B9") (pintype "passive"))
      (node (ref "U3") (pin "D1") (pinfunction "VSSQ3_D1") (pintype "passive"))
      (node (ref "U3") (pin "D8") (pinfunction "VSSQ4_D8") (pintype "passive"))
      (node (ref "U3") (pin "E1") (pinfunction "VSS3_E1") (pintype "passive"))
      (node (ref "U3") (pin "E2") (pinfunction "VSSQ5_E2") (pintype "passive"))
      (node (ref "U3") (pin "E8") (pinfunction "VSSQ6_E8") (pintype "passive"))
      (node (ref "U3") (pin "F9") (pinfunction "VSSQ7_F9") (pintype "passive"))
      (node (ref "U3") (pin "G1") (pinfunction "VSSQ8_G1") (pintype "passive"))
      (node (ref "U3") (pin "G8") (pinfunction "VSS4_G8") (pintype "passive"))
      (node (ref "U3") (pin "G9") (pinfunction "VSSQ9_G9") (pintype "passive"))
      (node (ref "U3") (pin "J2") (pinfunction "VSS5_J2") (pintype "passive"))
      (node (ref "U3") (pin "J8") (pinfunction "VSS6_J8") (pintype "passive"))
      (node (ref "U3") (pin "M1") (pinfunction "VSS7_M1") (pintype "passive"))
      (node (ref "U3") (pin "M9") (pinfunction "VSS8_M9") (pintype "passive"))
      (node (ref "U3") (pin "P1") (pinfunction "VSS9_P1") (pintype "passive"))
      (node (ref "U3") (pin "P9") (pinfunction "VSS10_P9") (pintype "passive"))
      (node (ref "U3") (pin "T1") (pinfunction "VSS11_T1") (pintype "passive"))
      (node (ref "U3") (pin "T9") (pinfunction "VSS12_T9") (pintype "passive"))
      (node (ref "U5") (pin "A9") (pinfunction "VSS1_A9") (pintype "passive"))
      (node (ref "U5") (pin "B1") (pinfunction "VSSQ1_B1") (pintype "passive"))
      (node (ref "U5") (pin "B3") (pinfunction "VSS2_B3") (pintype "passive"))
      (node (ref "U5") (pin "B9") (pinfunction "VSSQ2_B9") (pintype "passive"))
      (node (ref "U5") (pin "D1") (pinfunction "VSSQ3_D1") (pintype "passive"))
      (node (ref "U5") (pin "D8") (pinfunction "VSSQ4_D8") (pintype "passive"))
      (node (ref "U5") (pin "E1") (pinfunction "VSS3_E1") (pintype "passive"))
      (node (ref "U5") (pin "E2") (pinfunction "VSSQ5_E2") (pintype "passive"))
      (node (ref "U5") (pin "E8") (pinfunction "VSSQ6_E8") (pintype "passive"))
      (node (ref "U5") (pin "F9") (pinfunction "VSSQ7_F9") (pintype "passive"))
      (node (ref "U5") (pin "G1") (pinfunction "VSSQ8_G1") (pintype "passive"))
      (node (ref "U5") (pin "G8") (pinfunction "VSS4_G8") (pintype "passive"))
      (node (ref "U5") (pin "G9") (pinfunction "VSSQ9_G9") (pintype "passive"))
      (node (ref "U5") (pin "J2") (pinfunction "VSS5_J2") (pintype "passive"))
      (node (ref "U5") (pin "J8") (pinfunction "VSS6_J8") (pintype "passive"))
      (node (ref "U5") (pin "M1") (pinfunction "VSS7_M1") (pintype "passive"))
      (node (ref "U5") (pin "M9") (pinfunction "VSS8_M9") (pintype "passive"))
      (node (ref "U5") (pin "P1") (pinfunction "VSS9_P1") (pintype "passive"))
      (node (ref "U5") (pin "P9") (pinfunction "VSS10_P9") (pintype "passive"))
      (node (ref "U5") (pin "T1") (pinfunction "VSS11_T1") (pintype "passive"))
      (node (ref "U5") (pin "T9") (pinfunction "VSS12_T9") (pintype "passive"))
    )
    (net (code "78") (name "Net-(U1D-ZQPAD)") (class "Default")
      (node (ref "R107") (pin "2") (pinfunction "2_2") (pintype "passive"))
      (node (ref "U1") (pin "AE17") (pinfunction "ZQPAD_AE17") (pintype "passive"))
    )
    (net (code "79") (name "Net-(U3-ZQ)") (class "Default")
      (node (ref "R89") (pin "2") (pinfunction "2_2") (pintype "passive"))
      (node (ref "U3") (pin "L8") (pinfunction "ZQ_L8") (pintype "passive"))
    )
    (net (code "80") (name "Net-(U5-ZQ)") (class "Default")
      (node (ref "R599") (pin "2") (pinfunction "2_2") (pintype "passive"))
      (node (ref "U5") (pin "L8") (pinfunction "ZQ_L8") (pintype "passive"))
    )
    (net (code "81") (name "unconnected-(U1D-DRAM_CS1-PadAD17)") (class "Default")
      (node (ref "U1") (pin "AD17") (pinfunction "DRAM_CS1_AD17") (pintype "passive"))
    )
    (net (code "82") (name "unconnected-(U1D-DRAM_D32-PadAA17)") (class "Default")
      (node (ref "U1") (pin "AA17") (pinfunction "DRAM_D32_AA17") (pintype "passive"))
    )
    (net (code "83") (name "unconnected-(U1D-DRAM_D33-PadAA18)") (class "Default")
      (node (ref "U1") (pin "AA18") (pinfunction "DRAM_D33_AA18") (pintype "passive"))
    )
    (net (code "84") (name "unconnected-(U1D-DRAM_D34-PadAC18)") (class "Default")
      (node (ref "U1") (pin "AC18") (pinfunction "DRAM_D34_AC18") (pintype "passive"))
    )
    (net (code "85") (name "unconnected-(U1D-DRAM_D35-PadAE19)") (class "Default")
      (node (ref "U1") (pin "AE19") (pinfunction "DRAM_D35_AE19") (pintype "passive"))
    )
    (net (code "86") (name "unconnected-(U1D-DRAM_D36-PadY17)") (class "Default")
      (node (ref "U1") (pin "Y17") (pinfunction "DRAM_D36_Y17") (pintype "passive"))
    )
    (net (code "87") (name "unconnected-(U1D-DRAM_D37-PadY18)") (class "Default")
      (node (ref "U1") (pin "Y18") (pinfunction "DRAM_D37_Y18") (pintype "passive"))
    )
    (net (code "88") (name "unconnected-(U1D-DRAM_D38-PadAB19)") (class "Default")
      (node (ref "U1") (pin "AB19") (pinfunction "DRAM_D38_AB19") (pintype "passive"))
    )
    (net (code "89") (name "unconnected-(U1D-DRAM_D39-PadAC19)") (class "Default")
      (node (ref "U1") (pin "AC19") (pinfunction "DRAM_D39_AC19") (pintype "passive"))
    )
    (net (code "90") (name "unconnected-(U1D-DRAM_D40-PadY19)") (class "Default")
      (node (ref "U1") (pin "Y19") (pinfunction "DRAM_D40_Y19") (pintype "passive"))
    )
    (net (code "91") (name "unconnected-(U1D-DRAM_D41-PadAB20)") (class "Default")
      (node (ref "U1") (pin "AB20") (pinfunction "DRAM_D41_AB20") (pintype "passive"))
    )
    (net (code "92") (name "unconnected-(U1D-DRAM_D42-PadAB21)") (class "Default")
      (node (ref "U1") (pin "AB21") (pinfunction "DRAM_D42_AB21") (pintype "passive"))
    )
    (net (code "93") (name "unconnected-(U1D-DRAM_D43-PadAD21)") (class "Default")
      (node (ref "U1") (pin "AD21") (pinfunction "DRAM_D43_AD21") (pintype "passive"))
    )
    (net (code "94") (name "unconnected-(U1D-DRAM_D44-PadY20)") (class "Default")
      (node (ref "U1") (pin "Y20") (pinfunction "DRAM_D44_Y20") (pintype "passive"))
    )
    (net (code "95") (name "unconnected-(U1D-DRAM_D45-PadAA20)") (class "Default")
      (node (ref "U1") (pin "AA20") (pinfunction "DRAM_D45_AA20") (pintype "passive"))
    )
    (net (code "96") (name "unconnected-(U1D-DRAM_D46-PadAE21)") (class "Default")
      (node (ref "U1") (pin "AE21") (pinfunction "DRAM_D46_AE21") (pintype "passive"))
    )
    (net (code "97") (name "unconnected-(U1D-DRAM_D47-PadAC21)") (class "Default")
      (node (ref "U1") (pin "AC21") (pinfunction "DRAM_D47_AC21") (pintype "passive"))
    )
    (net (code "98") (name "unconnected-(U1D-DRAM_D48-PadAC22)") (class "Default")
      (node (ref "U1") (pin "AC22") (pinfunction "DRAM_D48_AC22") (pintype "passive"))
    )
    (net (code "99") (name "unconnected-(U1D-DRAM_D49-PadAE22)") (class "Default")
      (node (ref "U1") (pin "AE22") (pinfunction "DRAM_D49_AE22") (pintype "passive"))
    )
    (net (code "100") (name "unconnected-(U1D-DRAM_D50-PadAE24)") (class "Default")
      (node (ref "U1") (pin "AE24") (pinfunction "DRAM_D50_AE24") (pintype "passive"))
    )
    (net (code "101") (name "unconnected-(U1D-DRAM_D51-PadAC24)") (class "Default")
      (node (ref "U1") (pin "AC24") (pinfunction "DRAM_D51_AC24") (pintype "passive"))
    )
    (net (code "102") (name "unconnected-(U1D-DRAM_D52-PadAB22)") (class "Default")
      (node (ref "U1") (pin "AB22") (pinfunction "DRAM_D52_AB22") (pintype "passive"))
    )
    (net (code "103") (name "unconnected-(U1D-DRAM_D53-PadAC23)") (class "Default")
      (node (ref "U1") (pin "AC23") (pinfunction "DRAM_D53_AC23") (pintype "passive"))
    )
    (net (code "104") (name "unconnected-(U1D-DRAM_D54-PadAD25)") (class "Default")
      (node (ref "U1") (pin "AD25") (pinfunction "DRAM_D54_AD25") (pintype "passive"))
    )
    (net (code "105") (name "unconnected-(U1D-DRAM_D55-PadAC25)") (class "Default")
      (node (ref "U1") (pin "AC25") (pinfunction "DRAM_D55_AC25") (pintype "passive"))
    )
    (net (code "106") (name "unconnected-(U1D-DRAM_D56-PadAB25)") (class "Default")
      (node (ref "U1") (pin "AB25") (pinfunction "DRAM_D56_AB25") (pintype "passive"))
    )
    (net (code "107") (name "unconnected-(U1D-DRAM_D57-PadAA21)") (class "Default")
      (node (ref "U1") (pin "AA21") (pinfunction "DRAM_D57_AA21") (pintype "passive"))
    )
    (net (code "108") (name "unconnected-(U1D-DRAM_D58-PadY25)") (class "Default")
      (node (ref "U1") (pin "Y25") (pinfunction "DRAM_D58_Y25") (pintype "passive"))
    )
    (net (code "109") (name "unconnected-(U1D-DRAM_D59-PadY22)") (class "Default")
      (node (ref "U1") (pin "Y22") (pinfunction "DRAM_D59_Y22") (pintype "passive"))
    )
    (net (code "110") (name "unconnected-(U1D-DRAM_D60-PadAB23)") (class "Default")
      (node (ref "U1") (pin "AB23") (pinfunction "DRAM_D60_AB23") (pintype "passive"))
    )
    (net (code "111") (name "unconnected-(U1D-DRAM_D61-PadAA23)") (class "Default")
      (node (ref "U1") (pin "AA23") (pinfunction "DRAM_D61_AA23") (pintype "passive"))
    )
    (net (code "112") (name "unconnected-(U1D-DRAM_D62-PadY23)") (class "Default")
      (node (ref "U1") (pin "Y23") (pinfunction "DRAM_D62_Y23") (pintype "passive"))
    )
    (net (code "113") (name "unconnected-(U1D-DRAM_D63-PadW25)") (class "Default")
      (node (ref "U1") (pin "W25") (pinfunction "DRAM_D63_W25") (pintype "passive"))
    )
    (net (code "114") (name "unconnected-(U1D-DRAM_DQM4-PadAB18)") (class "Default")
      (node (ref "U1") (pin "AB18") (pinfunction "DRAM_DQM4_AB18") (pintype "passive"))
    )
    (net (code "115") (name "unconnected-(U1D-DRAM_DQM5-PadAC20)") (class "Default")
      (node (ref "U1") (pin "AC20") (pinfunction "DRAM_DQM5_AC20") (pintype "passive"))
    )
    (net (code "116") (name "unconnected-(U1D-DRAM_DQM6-PadAD24)") (class "Default")
      (node (ref "U1") (pin "AD24") (pinfunction "DRAM_DQM6_AD24") (pintype "passive"))
    )
    (net (code "117") (name "unconnected-(U1D-DRAM_DQM7-PadY21)") (class "Default")
      (node (ref "U1") (pin "Y21") (pinfunction "DRAM_DQM7_Y21") (pintype "passive"))
    )
    (net (code "118") (name "unconnected-(U1D-DRAM_SDCKE1-PadAA11)") (class "Default")
      (node (ref "U1") (pin "AA11") (pinfunction "DRAM_SDCKE1_AA11") (pintype "passive"))
    )
    (net (code "119") (name "unconnected-(U1D-DRAM_SDCLK_0-PadAD15)") (class "Default")
      (node (ref "U1") (pin "AD15") (pinfunction "DRAM_SDCLK_0_AD15") (pintype "passive"))
    )
    (net (code "120") (name "unconnected-(U1D-DRAM_SDODT1-PadAB17)") (class "Default")
      (node (ref "U1") (pin "AB17") (pinfunction "DRAM_SDODT1_AB17") (pintype "passive"))
    )
    (net (code "121") (name "unconnected-(U1D-DRAM_SDQS4-PadAD18)") (class "Default")
      (node (ref "U1") (pin "AD18") (pinfunction "DRAM_SDQS4_AD18") (pintype "passive"))
    )
    (net (code "122") (name "unconnected-(U1D-DRAM_SDQS5-PadAD20)") (class "Default")
      (node (ref "U1") (pin "AD20") (pinfunction "DRAM_SDQS5_AD20") (pintype "passive"))
    )
    (net (code "123") (name "unconnected-(U1D-DRAM_SDQS6-PadAD23)") (class "Default")
      (node (ref "U1") (pin "AD23") (pinfunction "DRAM_SDQS6_AD23") (pintype "passive"))
    )
    (net (code "124") (name "unconnected-(U1D-DRAM_SDQS7-PadAA25)") (class "Default")
      (node (ref "U1") (pin "AA25") (pinfunction "DRAM_SDQS7_AA25") (pintype "passive"))
    )
    (net (code "125") (name "unconnected-(U1D-~{DRAM_SDCLK_0_B}-PadAE15)") (class "Default")
      (node (ref "U1") (pin "AE15") (pinfunction "~{DRAM_SDCLK_0_B}_AE15") (pintype "passive"))
    )
    (net (code "126") (name "unconnected-(U1D-~{DRAM_SDQS4_B}-PadAE18)") (class "Default")
      (node (ref "U1") (pin "AE18") (pinfunction "~{DRAM_SDQS4_B}_AE18") (pintype "passive"))
    )
    (net (code "127") (name "unconnected-(U1D-~{DRAM_SDQS5_B}-PadAE20)") (class "Default")
      (node (ref "U1") (pin "AE20") (pinfunction "~{DRAM_SDQS5_B}_AE20") (pintype "passive"))
    )
    (net (code "128") (name "unconnected-(U1D-~{DRAM_SDQS6_B}-PadAE23)") (class "Default")
      (node (ref "U1") (pin "AE23") (pinfunction "~{DRAM_SDQS6_B}_AE23") (pintype "passive"))
    )
    (net (code "129") (name "unconnected-(U1D-~{DRAM_SDQS7_B}-PadAA24)") (class "Default")
      (node (ref "U1") (pin "AA24") (pinfunction "~{DRAM_SDQS7_B}_AA24") (pintype "passive"))
    )
    (net (code "130") (name "unconnected-(U3-NV_J1-PadJ1)") (class "Default")
      (node (ref "U3") (pin "J1") (pinfunction "NV_J1_J1") (pintype "passive"))
    )
    (net (code "131") (name "unconnected-(U3-NV_J9-PadJ9)") (class "Default")
      (node (ref "U3") (pin "J9") (pinfunction "NV_J9_J9") (pintype "passive"))
    )
    (net (code "132") (name "unconnected-(U3-NV_L1-PadL1)") (class "Default")
      (node (ref "U3") (pin "L1") (pinfunction "NV_L1_L1") (pintype "passive"))
    )
    (net (code "133") (name "unconnected-(U3-NV_L9-PadL9)") (class "Default")
      (node (ref "U3") (pin "L9") (pinfunction "NV_L9_L9") (pintype "passive"))
    )
    (net (code "134") (name "unconnected-(U5-NV_J1-PadJ1)") (class "Default")
      (node (ref "U5") (pin "J1") (pinfunction "NV_J1_J1") (pintype "passive"))
    )
    (net (code "135") (name "unconnected-(U5-NV_J9-PadJ9)") (class "Default")
      (node (ref "U5") (pin "J9") (pinfunction "NV_J9_J9") (pintype "passive"))
    )
    (net (code "136") (name "unconnected-(U5-NV_L1-PadL1)") (class "Default")
      (node (ref "U5") (pin "L1") (pinfunction "NV_L1_L1") (pintype "passive"))
    )
    (net (code "137") (name "unconnected-(U5-NV_L9-PadL9)") (class "Default")
      (node (ref "U5") (pin "L9") (pinfunction "NV_L9_L9") (pintype "passive"))
    )
  )
)
